# SolderingStation_Processor.net
KiCad netlist of a schematic drawn in Altium Designer
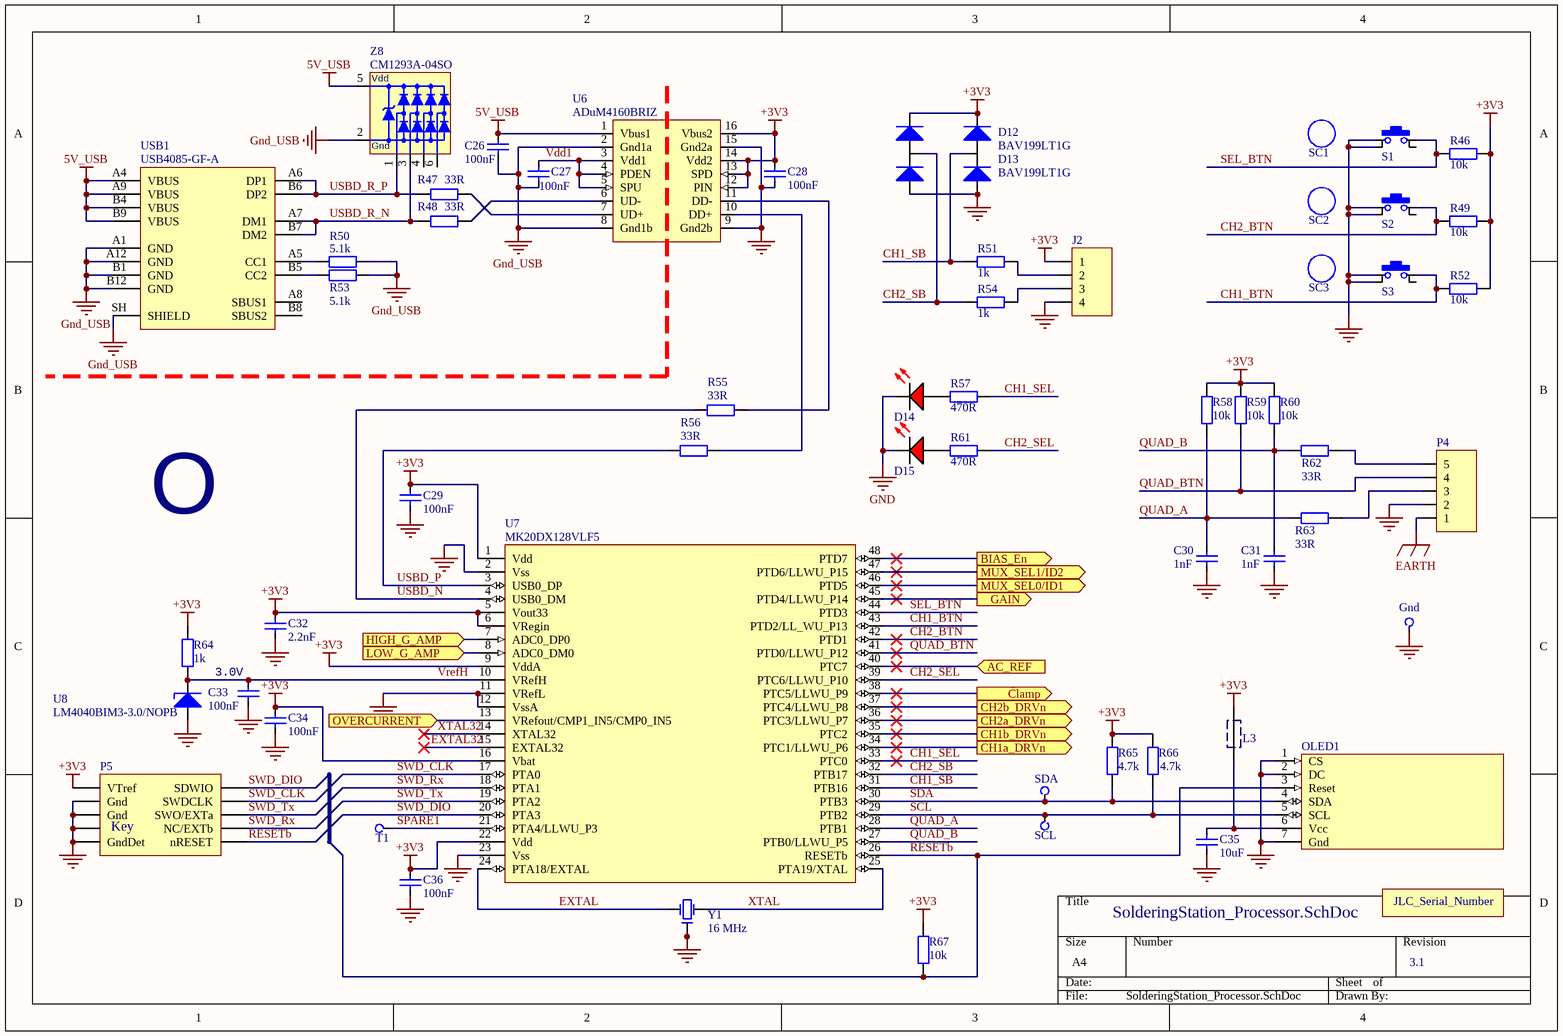
[diagram p0: SolderingStation_Processor.SchDoc]

(export (version "E")
  (design (tool "Eeschema 10.0.6"))
  (components
    (comp (ref "C26")
      (value "100nF")
      (footprint "CCNP1608-0603_N")
      (description "Capacitor non-polar SMT 0603")
      (fields
        (field (name "MANUFACTURER") "Generic Components")
        (field (name "PUBLISHER") "Altium Hobart Technology Centre")
      )
      (libsource (lib "MyLibrary") (part "Cap_CCNP_0603_100nF"))
    )
    (comp (ref "C27")
      (value "100nF")
      (footprint "CCNP1608-0603_N")
      (description "Capacitor non-polar SMT 0603")
      (fields
        (field (name "MANUFACTURER") "Generic Components")
        (field (name "PUBLISHER") "Altium Hobart Technology Centre")
      )
      (libsource (lib "MyLibrary") (part "Cap_CCNP_0603_100nF"))
    )
    (comp (ref "C28")
      (value "100nF")
      (footprint "CCNP1608-0603_N")
      (description "Capacitor non-polar SMT 0603")
      (fields
        (field (name "MANUFACTURER") "Generic Components")
        (field (name "PUBLISHER") "Altium Hobart Technology Centre")
      )
      (libsource (lib "MyLibrary") (part "Cap_CCNP_0603_100nF"))
    )
    (comp (ref "C29")
      (value "100nF")
      (footprint "CCNP1608-0603_N")
      (description "Capacitor non-polar SMT 0603")
      (fields
        (field (name "MANUFACTURER") "Generic Components")
        (field (name "PUBLISHER") "Altium Hobart Technology Centre")
      )
      (libsource (lib "MyLibrary") (part "Cap_CCNP_0603_100nF"))
    )
    (comp (ref "C30")
      (value "1nF")
      (footprint "CCNP1608-0603_N")
      (description "Capacitor non-polar SMT 0603")
      (fields
        (field (name "MANUFACTURER") "Generic Components")
        (field (name "PUBLISHER") "Altium Hobart Technology Centre")
      )
      (libsource (lib "MyLibrary") (part "Cap_CCNP_0603_1nF"))
    )
    (comp (ref "C31")
      (value "1nF")
      (footprint "CCNP1608-0603_N")
      (description "Capacitor non-polar SMT 0603")
      (fields
        (field (name "MANUFACTURER") "Generic Components")
        (field (name "PUBLISHER") "Altium Hobart Technology Centre")
      )
      (libsource (lib "MyLibrary") (part "Cap_CCNP_0603_1nF"))
    )
    (comp (ref "C32")
      (value "2.2nF")
      (footprint "CCNP1608-0603_N")
      (description "Capacitor non-polar SMT 0603")
      (fields
        (field (name "MANUFACTURER") "Generic Components")
        (field (name "PUBLISHER") "Altium Hobart Technology Centre")
      )
      (libsource (lib "MyLibrary") (part "Cap_CCNP_0603_2u2F"))
    )
    (comp (ref "C33")
      (value "100nF")
      (footprint "CCNP1608-0603_N")
      (description "Capacitor non-polar SMT 0603")
      (fields
        (field (name "MANUFACTURER") "Generic Components")
        (field (name "PUBLISHER") "Altium Hobart Technology Centre")
      )
      (libsource (lib "MyLibrary") (part "Cap_CCNP_0603_100nF"))
    )
    (comp (ref "C34")
      (value "100nF")
      (footprint "CCNP1608-0603_N")
      (description "Capacitor non-polar SMT 0603")
      (fields
        (field (name "MANUFACTURER") "Generic Components")
        (field (name "PUBLISHER") "Altium Hobart Technology Centre")
      )
      (libsource (lib "MyLibrary") (part "Cap_CCNP_0603_100nF"))
    )
    (comp (ref "C35")
      (value "10uF")
      (footprint "CCNP2012-0805")
      (description "Capacitor non-polar SMT 0805")
      (fields
        (field (name "MANUFACTURER") "Generic Components")
        (field (name "PUBLISHER") "Altium Hobart Technology Centre")
      )
      (libsource (lib "MyLibrary") (part "Cap_CCNP_0805_10uF"))
    )
    (comp (ref "C36")
      (value "100nF")
      (footprint "CCNP1608-0603_N")
      (description "Capacitor non-polar SMT 0603")
      (fields
        (field (name "MANUFACTURER") "Generic Components")
        (field (name "PUBLISHER") "Altium Hobart Technology Centre")
      )
      (libsource (lib "MyLibrary") (part "Cap_CCNP_0603_100nF"))
    )
    (comp (ref "D12")
      (value "BAV199LT1G")
      (footprint "SOT23_M")
      (description "Dual Series low-leakage switching diodes, 3-Pin SOT-23")
      (libsource (lib "MySchLib") (part "BAV199LT1G"))
    )
    (comp (ref "D13")
      (value "BAV199LT1G")
      (footprint "SOT23_M")
      (description "Dual Series low-leakage switching diodes, 3-Pin SOT-23")
      (libsource (lib "MySchLib") (part "BAV199LT1G"))
    )
    (comp (ref "D14")
      (value "LED")
      (footprint "LED3MM-RED - 10mm Proud")
      (description "3mm Red LED")
      (fields (field (name "MANUFACTURER") "Generic Components") (field (name "PUBLISHER") "Altium Limited"))
      (libsource (lib "MySchLib") (part "LED_3MM_RED"))
    )
    (comp (ref "D15")
      (value "LED")
      (footprint "LED3MM-RED - 10mm Proud")
      (description "3mm Red LED")
      (fields (field (name "MANUFACTURER") "Generic Components") (field (name "PUBLISHER") "Altium Limited"))
      (libsource (lib "MySchLib") (part "LED_3MM_RED"))
    )
    (comp (ref "Gnd")
      (value "Gnd")
      (footprint "PCBPIN - 0.9mm")
      (description "Test Point")
      (libsource (lib "MySchLib") (part "TP"))
    )
    (comp (ref "J2")
      (value "JST XH Connector, 4-Pin")
      (footprint "jst-b4b-xh-ax")
      (fields (field (name "PUBLISHER") "Altium Limited"))
      (libsource (lib "MyLibrary") (part "JST-B4B-XH-A"))
    )
    (comp (ref "JLC_Serial_Number1")
      (value "JLC_Serial_Number")
      (footprint "JLC_Serial_Number")
      (libsource (lib "MyLibrary") (part "JLC_Serial_Number"))
    )
    (comp (ref "L3")
      (value "Ferrite Bead")
      (footprint "FB2012-0805")
      (description "Ferrite Bead SMT 0805, TDK MPZ2012S102AT, 0.15OHM, 1.5A")
      (libsource (lib "MySchLib") (part "Ferrite Bead 0805"))
    )
    (comp (ref "Logo1")
      (value "OSHW Logo")
      (footprint "OSHW")
      (libsource (lib "MyLibrary") (part "OSHW Logo"))
    )
    (comp (ref "OLED1")
      (value "OLED_Display")
      (footprint "OLED_Display_128x64_2.4inch - no mounting holes")
      (description "OLED Display 128x64 pixels, 2.4inch")
      (libsource (lib "MySchLib") (part "OLED_Display_128x64_2.4inch"))
    )
    (comp (ref "P4")
      (value "Header, 5-Pin")
      (footprint "HDR1X5S")
      (fields (field (name "PUBLISHER") "Altium Limited"))
      (libsource (lib "MyLibrary") (part "Header 1x5"))
    )
    (comp (ref "P5")
      (value "SWD Connector 2x5-Pin")
      (footprint "SWD-2x5-Jig-Header")
      (fields (field (name "PUBLISHER") "Altium Limited"))
      (libsource (lib "MySchLib") (part "SWD2X5_JIG"))
    )
    (comp (ref "R46")
      (value "10k")
      (footprint "CR1608-0603_N")
      (description "Resistor SMT 0603")
      (fields
        (field (name "MANUFACTURER") "Generic Components")
        (field (name "PUBLISHER") "Altium Hobart Technology Centre")
      )
      (libsource (lib "") (part "Res_CR0603_10k_1"))
    )
    (comp (ref "R47")
      (value "33R")
      (footprint "CR1608-0603_N")
      (description "Resistor SMT 0603")
      (fields
        (field (name "MANUFACTURER") "Generic Components")
        (field (name "PUBLISHER") "Altium Hobart Technology Centre")
      )
      (libsource (lib "MyLibrary") (part "Res_CR0603_33R"))
    )
    (comp (ref "R48")
      (value "33R")
      (footprint "CR1608-0603_N")
      (description "Resistor SMT 0603")
      (fields
        (field (name "MANUFACTURER") "Generic Components")
        (field (name "PUBLISHER") "Altium Hobart Technology Centre")
      )
      (libsource (lib "MyLibrary") (part "Res_CR0603_33R"))
    )
    (comp (ref "R49")
      (value "10k")
      (footprint "CR1608-0603_N")
      (description "Resistor SMT 0603")
      (fields
        (field (name "MANUFACTURER") "Generic Components")
        (field (name "PUBLISHER") "Altium Hobart Technology Centre")
      )
      (libsource (lib "") (part "Res_CR0603_10k_1"))
    )
    (comp (ref "R50")
      (value "5.1k")
      (footprint "CR1608-0603_N")
      (description "Resistor SMT 0603")
      (fields
        (field (name "MANUFACTURER") "Generic Components")
        (field (name "PUBLISHER") "Altium Hobart Technology Centre")
      )
      (libsource (lib "MyLibrary") (part "Res_CR0603_5k1"))
    )
    (comp (ref "R51")
      (value "1k")
      (footprint "CR1608-0603_N")
      (description "Resistor SMT 0603")
      (fields
        (field (name "MANUFACTURER") "Generic Components")
        (field (name "PUBLISHER") "Altium Hobart Technology Centre")
      )
      (libsource (lib "") (part "Res_CR0603_1k_1"))
    )
    (comp (ref "R52")
      (value "10k")
      (footprint "CR1608-0603_N")
      (description "Resistor SMT 0603")
      (fields
        (field (name "MANUFACTURER") "Generic Components")
        (field (name "PUBLISHER") "Altium Hobart Technology Centre")
      )
      (libsource (lib "") (part "Res_CR0603_10k_1"))
    )
    (comp (ref "R53")
      (value "5.1k")
      (footprint "CR1608-0603_N")
      (description "Resistor SMT 0603")
      (fields
        (field (name "MANUFACTURER") "Generic Components")
        (field (name "PUBLISHER") "Altium Hobart Technology Centre")
      )
      (libsource (lib "MyLibrary") (part "Res_CR0603_5k1"))
    )
    (comp (ref "R54")
      (value "1k")
      (footprint "CR1608-0603_N")
      (description "Resistor SMT 0603")
      (fields
        (field (name "MANUFACTURER") "Generic Components")
        (field (name "PUBLISHER") "Altium Hobart Technology Centre")
      )
      (libsource (lib "") (part "Res_CR0603_1k_1"))
    )
    (comp (ref "R55")
      (value "33R")
      (footprint "CR1608-0603_N")
      (description "Resistor SMT 0603")
      (fields
        (field (name "MANUFACTURER") "Generic Components")
        (field (name "PUBLISHER") "Altium Hobart Technology Centre")
      )
      (libsource (lib "MyLibrary") (part "Res_CR0603_33R"))
    )
    (comp (ref "R56")
      (value "33R")
      (footprint "CR1608-0603_N")
      (description "Resistor SMT 0603")
      (fields
        (field (name "MANUFACTURER") "Generic Components")
        (field (name "PUBLISHER") "Altium Hobart Technology Centre")
      )
      (libsource (lib "MyLibrary") (part "Res_CR0603_33R"))
    )
    (comp (ref "R57")
      (value "470R")
      (footprint "CR1608-0603_N")
      (description "Resistor SMT 0603")
      (fields
        (field (name "MANUFACTURER") "Generic Components")
        (field (name "PUBLISHER") "Altium Hobart Technology Centre")
      )
      (libsource (lib "MyLibrary") (part "Res_CR0603_470R"))
    )
    (comp (ref "R58")
      (value "10k")
      (footprint "CR1608-0603_N")
      (description "Resistor SMT 0603")
      (fields
        (field (name "MANUFACTURER") "Generic Components")
        (field (name "PUBLISHER") "Altium Hobart Technology Centre")
      )
      (libsource (lib "MyLibrary") (part "Res_CR0603_10k"))
    )
    (comp (ref "R59")
      (value "10k")
      (footprint "CR1608-0603_N")
      (description "Resistor SMT 0603")
      (fields
        (field (name "MANUFACTURER") "Generic Components")
        (field (name "PUBLISHER") "Altium Hobart Technology Centre")
      )
      (libsource (lib "MyLibrary") (part "Res_CR0603_10k"))
    )
    (comp (ref "R60")
      (value "10k")
      (footprint "CR1608-0603_N")
      (description "Resistor SMT 0603")
      (fields
        (field (name "MANUFACTURER") "Generic Components")
        (field (name "PUBLISHER") "Altium Hobart Technology Centre")
      )
      (libsource (lib "MyLibrary") (part "Res_CR0603_10k"))
    )
    (comp (ref "R61")
      (value "470R")
      (footprint "CR1608-0603_N")
      (description "Resistor SMT 0603")
      (fields
        (field (name "MANUFACTURER") "Generic Components")
        (field (name "PUBLISHER") "Altium Hobart Technology Centre")
      )
      (libsource (lib "") (part "Res_CR0603_470R_1"))
    )
    (comp (ref "R62")
      (value "33R")
      (footprint "CR1608-0603_N")
      (description "Resistor SMT 0603")
      (fields
        (field (name "MANUFACTURER") "Generic Components")
        (field (name "PUBLISHER") "Altium Hobart Technology Centre")
      )
      (libsource (lib "MyLibrary") (part "Res_CR0603_33R"))
    )
    (comp (ref "R63")
      (value "33R")
      (footprint "CR1608-0603_N")
      (description "Resistor SMT 0603")
      (fields
        (field (name "MANUFACTURER") "Generic Components")
        (field (name "PUBLISHER") "Altium Hobart Technology Centre")
      )
      (libsource (lib "MyLibrary") (part "Res_CR0603_33R"))
    )
    (comp (ref "R64")
      (value "1k")
      (footprint "CR1608-0603_N")
      (description "Resistor SMT 0603")
      (fields
        (field (name "MANUFACTURER") "Generic Components")
        (field (name "PUBLISHER") "Altium Hobart Technology Centre")
      )
      (libsource (lib "MyLibrary") (part "Res_CR0603_1k"))
    )
    (comp (ref "R65")
      (value "4.7k")
      (footprint "CR1608-0603_N")
      (description "Resistor SMT 0603")
      (fields
        (field (name "MANUFACTURER") "Generic Components")
        (field (name "PUBLISHER") "Altium Hobart Technology Centre")
      )
      (libsource (lib "MyLibrary") (part "Res_CR0603_4k7"))
    )
    (comp (ref "R66")
      (value "4.7k")
      (footprint "CR1608-0603_N")
      (description "Resistor SMT 0603")
      (fields
        (field (name "MANUFACTURER") "Generic Components")
        (field (name "PUBLISHER") "Altium Hobart Technology Centre")
      )
      (libsource (lib "MyLibrary") (part "Res_CR0603_4k7"))
    )
    (comp (ref "R67")
      (value "10k")
      (footprint "CR1608-0603_N")
      (description "Resistor SMT 0603")
      (fields
        (field (name "MANUFACTURER") "Generic Components")
        (field (name "PUBLISHER") "Altium Hobart Technology Centre")
      )
      (libsource (lib "MyLibrary") (part "Res_CR0603_10k"))
    )
    (comp (ref "S1")
      (value "SW_PB-B3F1052")
      (footprint "SW_MIN_PB-B3F1052")
      (description "Switch miniature push-button")
      (fields (field (name "MANUFACTURER") "Generic Components") (field (name "PUBLISHER") "Altium Limited"))
      (libsource (lib "MySchLib") (part "SW_PB-B3F1052"))
    )
    (comp (ref "S2")
      (value "SW_PB-B3F1052")
      (footprint "SW_MIN_PB-B3F1052")
      (description "Switch miniature push-button")
      (fields (field (name "MANUFACTURER") "Generic Components") (field (name "PUBLISHER") "Altium Limited"))
      (libsource (lib "MySchLib") (part "SW_PB-B3F1052"))
    )
    (comp (ref "S3")
      (value "SW_PB-B3F1052")
      (footprint "SW_MIN_PB-B3F1052")
      (description "Switch miniature push-button")
      (fields (field (name "MANUFACTURER") "Generic Components") (field (name "PUBLISHER") "Altium Limited"))
      (libsource (lib "MySchLib") (part "SW_PB-B3F1052"))
    )
    (comp (ref "SC1")
      (value "B32-2010")
      (footprint "SW-CAP-B32-2010")
      (description "Switch Cap")
      (libsource (lib "MySchLib") (part "Switch-Cap - B32-2010"))
    )
    (comp (ref "SC2")
      (value "B32-2010")
      (footprint "SW-CAP-B32-2010")
      (description "Switch Cap")
      (libsource (lib "MySchLib") (part "Switch-Cap - B32-2010"))
    )
    (comp (ref "SC3")
      (value "B32-2010")
      (footprint "SW-CAP-B32-2010")
      (description "Switch Cap")
      (libsource (lib "MySchLib") (part "Switch-Cap - B32-2010"))
    )
    (comp (ref "SCL")
      (value "SCL")
      (footprint "PCBPIN - 0.9mm")
      (description "Test Point")
      (libsource (lib "MySchLib") (part "TP"))
    )
    (comp (ref "SDA")
      (value "SDA")
      (footprint "PCBPIN - 0.9mm")
      (description "Test Point")
      (libsource (lib "MySchLib") (part "TP"))
    )
    (comp (ref "T1")
      (value "PTA4")
      (footprint "PCBPIN - 0.9mm")
      (description "Test Point")
      (libsource (lib "MySchLib") (part "TP"))
    )
    (comp (ref "U6")
      (value "ADuM4160BRIZ")
      (footprint "SOIC127P1030-16M")
      (description "Full/Low Speed 5 kV USB Digital Isolator")
      (libsource (lib "MySchLib") (part "ADuM4160BRIZ"))
    )
    (comp (ref "U7")
      (value "MK20DX128VLF5")
      (footprint "TSQFP50P900X900-48M")
      (description "Kinetis K20: 50MHz Cortex-M4 Performance MCU, 160KB Flash, 16KB SRAM, Full-Speed USB, 48-LQFP")
      (libsource (lib "MySchLib") (part "MK20DX128VLF5"))
    )
    (comp (ref "U8")
      (value "LM4040BIM3-3.0/NOPB")
      (footprint "SOT23_M")
      (description "IC 2.5V VREF SHUNT 0.2% SOT23-3")
      (libsource (lib "MySchLib") (part "LM4040BIM3-2.5/NOPB"))
    )
    (comp (ref "USB1")
      (value "USB4085-GF-A")
      (footprint "USB4085-GF-A")
      (description "USB-C, USB 2.0 Receptacle Connector 16 Position Through Hole, Right Angle")
      (fields (field (name "DIGIKEY PART NUMBER") "2073-USB4085-GF-ACT-ND"))
      (libsource (lib "MyLibrary") (part "USB4085-GF-A"))
    )
    (comp (ref "Y1")
      (value "16 MHz")
      (footprint "Crystal_SMD_3.2x2.5")
      (description "Crystal SMD 3.2 x 2.5 x 0.7 mm")
      (fields
        (field (name "MANUFACTURER") "Generic Components")
        (field (name "PUBLISHER") "Altium Hobart Technology Centre")
      )
      (libsource (lib "MyLibrary") (part "Crystal 16MHz"))
    )
    (comp (ref "Z8")
      (value "CM1293A-04SO")
      (footprint "SOT457_M - 180")
      (description "Ultra low capacitance quadruple rail-to-rail ESD protection")
      (libsource (lib "MySchLib") (part "CM1293A-04SO"))
    )
  )
  (nets
    (net (code "1") (name "+3V3") (class "Default")
      (node (ref "C28") (pin "2") (pinfunction "2_2") (pintype "passive"))
      (node (ref "C29") (pin "2") (pinfunction "2_2") (pintype "passive"))
      (node (ref "C32") (pin "2") (pinfunction "2_2") (pintype "passive"))
      (node (ref "C34") (pin "2") (pinfunction "2_2") (pintype "passive"))
      (node (ref "C36") (pin "2") (pinfunction "2_2") (pintype "passive"))
      (node (ref "D12") (pin "2") (pinfunction "A2_2") (pintype "passive"))
      (node (ref "D13") (pin "2") (pinfunction "A2_2") (pintype "passive"))
      (node (ref "J2") (pin "1") (pinfunction "1_1") (pintype "passive"))
      (node (ref "L3") (pin "1") (pinfunction "1_1") (pintype "passive"))
      (node (ref "P5") (pin "1") (pinfunction "VTref_1") (pintype "passive"))
      (node (ref "R46") (pin "2") (pinfunction "2_2") (pintype "passive"))
      (node (ref "R49") (pin "2") (pinfunction "2_2") (pintype "passive"))
      (node (ref "R52") (pin "2") (pinfunction "2_2") (pintype "passive"))
      (node (ref "R58") (pin "2") (pinfunction "2_2") (pintype "passive"))
      (node (ref "R59") (pin "2") (pinfunction "2_2") (pintype "passive"))
      (node (ref "R60") (pin "2") (pinfunction "2_2") (pintype "passive"))
      (node (ref "R64") (pin "1") (pinfunction "1_1") (pintype "passive"))
      (node (ref "R65") (pin "2") (pinfunction "2_2") (pintype "passive"))
      (node (ref "R66") (pin "2") (pinfunction "2_2") (pintype "passive"))
      (node (ref "R67") (pin "2") (pinfunction "2_2") (pintype "passive"))
      (node (ref "U6") (pin "12") (pinfunction "PIN_12") (pintype "input"))
      (node (ref "U6") (pin "13") (pinfunction "SPD_13") (pintype "input"))
      (node (ref "U6") (pin "14") (pinfunction "Vdd2_14") (pintype "power_in"))
      (node (ref "U6") (pin "16") (pinfunction "Vbus2_16") (pintype "power_in"))
      (node (ref "U7") (pin "1") (pinfunction "Vdd_1") (pintype "power_in"))
      (node (ref "U7") (pin "16") (pinfunction "Vbat_16") (pintype "passive"))
      (node (ref "U7") (pin "22") (pinfunction "Vdd_22") (pintype "power_in"))
      (node (ref "U7") (pin "5") (pinfunction "Vout33_5") (pintype "power_in"))
      (node (ref "U7") (pin "6") (pinfunction "VRegin_6") (pintype "passive"))
      (node (ref "U7") (pin "9") (pinfunction "VddA_9") (pintype "power_in"))
    )
    (net (code "2") (name "/AC_REF") (class "Default")
      (node (ref "U7") (pin "40") (pinfunction "PTC7_40") (pintype "bidirectional"))
    )
    (net (code "3") (name "/BIAS_En") (class "Default")
      (node (ref "U7") (pin "48") (pinfunction "PTD7_48") (pintype "bidirectional"))
    )
    (net (code "4") (name "/CH1_BTN") (class "Default")
      (node (ref "R52") (pin "1") (pinfunction "1_1") (pintype "passive"))
      (node (ref "S3") (pin "2") (pinfunction "2_2") (pintype "passive"))
      (node (ref "U7") (pin "43") (pinfunction "PTD2/LL_WU_P13_43") (pintype "bidirectional"))
    )
    (net (code "5") (name "/CH1_SB") (class "Default")
      (node (ref "D13") (pin "3") (pinfunction "K_3") (pintype "passive"))
      (node (ref "R51") (pin "1") (pinfunction "1_1") (pintype "passive"))
      (node (ref "U7") (pin "31") (pinfunction "PTB16_31") (pintype "bidirectional"))
    )
    (net (code "6") (name "/CH1_SEL") (class "Default")
      (node (ref "R57") (pin "1") (pinfunction "1_1") (pintype "passive"))
      (node (ref "U7") (pin "33") (pinfunction "PTC0_33") (pintype "bidirectional"))
    )
    (net (code "7") (name "/CH1a_DRVn") (class "Default")
      (node (ref "U7") (pin "34") (pinfunction "PTC1/LLWU_P6_34") (pintype "bidirectional"))
    )
    (net (code "8") (name "/CH1b_DRVn") (class "Default")
      (node (ref "U7") (pin "35") (pinfunction "PTC2_35") (pintype "bidirectional"))
    )
    (net (code "9") (name "/CH2_BTN") (class "Default")
      (node (ref "R49") (pin "1") (pinfunction "1_1") (pintype "passive"))
      (node (ref "S2") (pin "2") (pinfunction "2_2") (pintype "passive"))
      (node (ref "U7") (pin "42") (pinfunction "PTD1_42") (pintype "bidirectional"))
    )
    (net (code "10") (name "/CH2_SB") (class "Default")
      (node (ref "D12") (pin "3") (pinfunction "K_3") (pintype "passive"))
      (node (ref "R54") (pin "1") (pinfunction "1_1") (pintype "passive"))
      (node (ref "U7") (pin "32") (pinfunction "PTB17_32") (pintype "bidirectional"))
    )
    (net (code "11") (name "/CH2_SEL") (class "Default")
      (node (ref "R61") (pin "2") (pinfunction "2_2") (pintype "passive"))
      (node (ref "U7") (pin "39") (pinfunction "PTC6/LLWU_P10_39") (pintype "bidirectional"))
    )
    (net (code "12") (name "/CH2a_DRVn") (class "Default")
      (node (ref "U7") (pin "36") (pinfunction "PTC3/LLWU_P7_36") (pintype "bidirectional"))
    )
    (net (code "13") (name "/CH2b_DRVn") (class "Default")
      (node (ref "U7") (pin "37") (pinfunction "PTC4/LLWU_P8_37") (pintype "bidirectional"))
    )
    (net (code "14") (name "/Clamp") (class "Default")
      (node (ref "U7") (pin "38") (pinfunction "PTC5/LLWU_P9_38") (pintype "bidirectional"))
    )
    (net (code "15") (name "/EXTAL") (class "Default")
      (node (ref "U7") (pin "24") (pinfunction "PTA18/EXTAL_24") (pintype "bidirectional"))
      (node (ref "Y1") (pin "3") (pinfunction "OSC2_3") (pintype "passive"))
    )
    (net (code "16") (name "/EXTAL32") (class "Default")
      (node (ref "U7") (pin "15") (pinfunction "EXTAL32_15") (pintype "passive+no_connect"))
    )
    (net (code "17") (name "/GAIN") (class "Default")
      (node (ref "U7") (pin "45") (pinfunction "PTD4/LLWU_P14_45") (pintype "bidirectional"))
    )
    (net (code "18") (name "/HIGH_G_AMP") (class "Default")
      (node (ref "U7") (pin "7") (pinfunction "ADC0_DP0_7") (pintype "input"))
    )
    (net (code "19") (name "/LOW_G_AMP") (class "Default")
      (node (ref "U7") (pin "8") (pinfunction "ADC0_DM0_8") (pintype "input"))
    )
    (net (code "20") (name "/MUX_SEL0{slash}ID1") (class "Default")
      (node (ref "U7") (pin "46") (pinfunction "PTD5_46") (pintype "bidirectional"))
    )
    (net (code "21") (name "/MUX_SEL1{slash}ID2") (class "Default")
      (node (ref "U7") (pin "47") (pinfunction "PTD6/LLWU_P15_47") (pintype "bidirectional"))
    )
    (net (code "22") (name "/OVERCURRENT") (class "Default")
      (node (ref "U7") (pin "13") (pinfunction "VRefout/CMP1_IN5/CMP0_IN5_13") (pintype "passive"))
    )
    (net (code "23") (name "/QUAD_A") (class "Default")
      (node (ref "C30") (pin "2") (pinfunction "2_2") (pintype "passive"))
      (node (ref "R58") (pin "1") (pinfunction "1_1") (pintype "passive"))
      (node (ref "R63") (pin "2") (pinfunction "2_2") (pintype "passive"))
      (node (ref "U7") (pin "28") (pinfunction "PTB1_28") (pintype "bidirectional"))
    )
    (net (code "24") (name "/QUAD_B") (class "Default")
      (node (ref "C31") (pin "2") (pinfunction "2_2") (pintype "passive"))
      (node (ref "R60") (pin "1") (pinfunction "1_1") (pintype "passive"))
      (node (ref "R62") (pin "2") (pinfunction "2_2") (pintype "passive"))
      (node (ref "U7") (pin "27") (pinfunction "PTB0/LLWU_P5_27") (pintype "bidirectional"))
    )
    (net (code "25") (name "/QUAD_BTN") (class "Default")
      (node (ref "P4") (pin "4") (pinfunction "4_4") (pintype "passive"))
      (node (ref "R59") (pin "1") (pinfunction "1_1") (pintype "passive"))
      (node (ref "U7") (pin "41") (pinfunction "PTD0/LLWU_P12_41") (pintype "bidirectional"))
    )
    (net (code "26") (name "/RESETb") (class "Default")
      (node (ref "OLED1") (pin "3") (pinfunction "Reset_3") (pintype "input"))
      (node (ref "P5") (pin "10") (pinfunction "nRESET_10") (pintype "passive"))
      (node (ref "R67") (pin "1") (pinfunction "1_1") (pintype "passive"))
      (node (ref "U7") (pin "26") (pinfunction "RESETb_26") (pintype "bidirectional"))
    )
    (net (code "27") (name "/SCL") (class "Default")
      (node (ref "OLED1") (pin "5") (pinfunction "SCL_5") (pintype "bidirectional"))
      (node (ref "R66") (pin "1") (pinfunction "1_1") (pintype "passive"))
      (node (ref "SCL") (pin "1") (pinfunction "TP_1") (pintype "passive"))
      (node (ref "U7") (pin "29") (pinfunction "PTB2_29") (pintype "bidirectional"))
    )
    (net (code "28") (name "/SDA") (class "Default")
      (node (ref "OLED1") (pin "4") (pinfunction "SDA_4") (pintype "bidirectional"))
      (node (ref "R65") (pin "1") (pinfunction "1_1") (pintype "passive"))
      (node (ref "SDA") (pin "1") (pinfunction "TP_1") (pintype "passive"))
      (node (ref "U7") (pin "30") (pinfunction "PTB3_30") (pintype "bidirectional"))
    )
    (net (code "29") (name "/SEL_BTN") (class "Default")
      (node (ref "R46") (pin "1") (pinfunction "1_1") (pintype "passive"))
      (node (ref "S1") (pin "2") (pinfunction "2_2") (pintype "passive"))
      (node (ref "U7") (pin "44") (pinfunction "PTD3_44") (pintype "bidirectional"))
    )
    (net (code "30") (name "/SPARE1") (class "Default")
      (node (ref "T1") (pin "1") (pinfunction "TP_1") (pintype "passive"))
      (node (ref "U7") (pin "21") (pinfunction "PTA4/LLWU_P3_21") (pintype "bidirectional"))
    )
    (net (code "31") (name "/SWD_CLK") (class "Default")
      (node (ref "P5") (pin "4") (pinfunction "SWDCLK_4") (pintype "passive"))
      (node (ref "U7") (pin "17") (pinfunction "PTA0_17") (pintype "bidirectional"))
    )
    (net (code "32") (name "/SWD_DIO") (class "Default")
      (node (ref "P5") (pin "2") (pinfunction "SDWIO_2") (pintype "passive"))
      (node (ref "U7") (pin "20") (pinfunction "PTA3_20") (pintype "bidirectional"))
    )
    (net (code "33") (name "/SWD_Rx") (class "Default")
      (node (ref "P5") (pin "8") (pinfunction "NC/EXTb_8") (pintype "passive"))
      (node (ref "U7") (pin "18") (pinfunction "PTA1_18") (pintype "bidirectional"))
    )
    (net (code "34") (name "/SWD_Tx") (class "Default")
      (node (ref "P5") (pin "6") (pinfunction "SWO/EXTa_6") (pintype "passive"))
      (node (ref "U7") (pin "19") (pinfunction "PTA2_19") (pintype "bidirectional"))
    )
    (net (code "35") (name "/USBD_N") (class "Default")
      (node (ref "R55") (pin "2") (pinfunction "2_2") (pintype "passive"))
      (node (ref "U7") (pin "4") (pinfunction "USB0_DM_4") (pintype "bidirectional"))
    )
    (net (code "36") (name "/USBD_P") (class "Default")
      (node (ref "R56") (pin "2") (pinfunction "2_2") (pintype "passive"))
      (node (ref "U7") (pin "3") (pinfunction "USB0_DP_3") (pintype "bidirectional"))
    )
    (net (code "37") (name "/USBD_R_N") (class "Default")
      (node (ref "R48") (pin "2") (pinfunction "2_2") (pintype "passive"))
      (node (ref "USB1") (pin "A7") (pinfunction "DM1_A7") (pintype "passive"))
      (node (ref "USB1") (pin "B7") (pinfunction "DM2_B7") (pintype "passive"))
      (node (ref "Z8") (pin "3") (pintype "passive"))
    )
    (net (code "38") (name "/USBD_R_P") (class "Default")
      (node (ref "R47") (pin "2") (pinfunction "2_2") (pintype "passive"))
      (node (ref "USB1") (pin "A6") (pinfunction "DP1_A6") (pintype "passive"))
      (node (ref "USB1") (pin "B6") (pinfunction "DP2_B6") (pintype "passive"))
      (node (ref "Z8") (pin "1") (pintype "passive"))
    )
    (net (code "39") (name "/Vdd1") (class "Default")
      (node (ref "C27") (pin "2") (pinfunction "2_2") (pintype "passive"))
      (node (ref "U6") (pin "3") (pinfunction "Vdd1_3") (pintype "power_in"))
      (node (ref "U6") (pin "4") (pinfunction "PDEN_4") (pintype "input"))
      (node (ref "U6") (pin "5") (pinfunction "SPU_5") (pintype "input"))
    )
    (net (code "40") (name "/VrefH") (class "Default")
      (node (ref "C33") (pin "2") (pinfunction "2_2") (pintype "passive"))
      (node (ref "R64") (pin "2") (pinfunction "2_2") (pintype "passive"))
      (node (ref "U7") (pin "10") (pinfunction "VRefH_10") (pintype "passive"))
      (node (ref "U8") (pin "1") (pinfunction "K_1") (pintype "passive"))
    )
    (net (code "41") (name "/XTAL") (class "Default")
      (node (ref "U7") (pin "25") (pinfunction "PTA19/XTAL_25") (pintype "bidirectional"))
      (node (ref "Y1") (pin "1") (pinfunction "OSC1_1") (pintype "passive"))
    )
    (net (code "42") (name "/XTAL32") (class "Default")
      (node (ref "U7") (pin "14") (pinfunction "XTAL32_14") (pintype "passive+no_connect"))
    )
    (net (code "43") (name "5V_USB") (class "Default")
      (node (ref "C26") (pin "2") (pinfunction "2_2") (pintype "passive"))
      (node (ref "U6") (pin "1") (pinfunction "Vbus1_1") (pintype "power_in"))
      (node (ref "USB1") (pin "A4") (pinfunction "VBUS_A4") (pintype "passive"))
      (node (ref "USB1") (pin "A9") (pinfunction "VBUS_A9") (pintype "passive"))
      (node (ref "USB1") (pin "B4") (pinfunction "VBUS_B4") (pintype "passive"))
      (node (ref "USB1") (pin "B9") (pinfunction "VBUS_B9") (pintype "passive"))
      (node (ref "Z8") (pin "5") (pinfunction "Vp_5") (pintype "passive"))
    )
    (net (code "44") (name "EARTH") (class "Default")
      (node (ref "P4") (pin "1") (pinfunction "1_1") (pintype "passive"))
    )
    (net (code "45") (name "GND") (class "Default")
      (node (ref "C28") (pin "1") (pinfunction "1_1") (pintype "passive"))
      (node (ref "C29") (pin "1") (pinfunction "1_1") (pintype "passive"))
      (node (ref "C30") (pin "1") (pinfunction "1_1") (pintype "passive"))
      (node (ref "C31") (pin "1") (pinfunction "1_1") (pintype "passive"))
      (node (ref "C32") (pin "1") (pinfunction "1_1") (pintype "passive"))
      (node (ref "C33") (pin "1") (pinfunction "1_1") (pintype "passive"))
      (node (ref "C34") (pin "1") (pinfunction "1_1") (pintype "passive"))
      (node (ref "C35") (pin "1") (pinfunction "1_1") (pintype "passive"))
      (node (ref "C36") (pin "1") (pinfunction "1_1") (pintype "passive"))
      (node (ref "D12") (pin "1") (pinfunction "A1_1") (pintype "passive"))
      (node (ref "D13") (pin "1") (pinfunction "A1_1") (pintype "passive"))
      (node (ref "D14") (pin "K") (pinfunction "K_K") (pintype "passive"))
      (node (ref "D15") (pin "K") (pinfunction "K_K") (pintype "passive"))
      (node (ref "Gnd") (pin "1") (pinfunction "TP_1") (pintype "passive"))
      (node (ref "J2") (pin "4") (pinfunction "4_4") (pintype "passive"))
      (node (ref "OLED1") (pin "1") (pinfunction "CS_1") (pintype "input"))
      (node (ref "OLED1") (pin "2") (pinfunction "DC_2") (pintype "input"))
      (node (ref "OLED1") (pin "7") (pinfunction "Gnd_7") (pintype "power_in"))
      (node (ref "P4") (pin "2") (pinfunction "2_2") (pintype "passive"))
      (node (ref "P5") (pin "0") (pinfunction "Pins_0") (pintype "power_in"))
      (node (ref "P5") (pin "3") (pinfunction "Gnd_3") (pintype "passive"))
      (node (ref "P5") (pin "5") (pinfunction "Gnd_5") (pintype "passive"))
      (node (ref "P5") (pin "9") (pinfunction "GndDet_9") (pintype "passive"))
      (node (ref "S1") (pin "1") (pinfunction "1_1") (pintype "passive"))
      (node (ref "S1") (pin "1b") (pinfunction "1b_1b") (pintype "passive"))
      (node (ref "S2") (pin "1") (pinfunction "1_1") (pintype "passive"))
      (node (ref "S2") (pin "1b") (pinfunction "1b_1b") (pintype "passive"))
      (node (ref "S3") (pin "1") (pinfunction "1_1") (pintype "passive"))
      (node (ref "S3") (pin "1b") (pinfunction "1b_1b") (pintype "passive"))
      (node (ref "U6") (pin "15") (pinfunction "Gnd2a_15") (pintype "power_in"))
      (node (ref "U6") (pin "9") (pinfunction "Gnd2b_9") (pintype "power_in"))
      (node (ref "U7") (pin "11") (pinfunction "VRefL_11") (pintype "passive"))
      (node (ref "U7") (pin "12") (pinfunction "VssA_12") (pintype "power_in"))
      (node (ref "U7") (pin "2") (pinfunction "Vss_2") (pintype "power_in"))
      (node (ref "U7") (pin "23") (pinfunction "Vss_23") (pintype "power_in"))
      (node (ref "U8") (pin "2") (pinfunction "A_2") (pintype "passive"))
      (node (ref "Y1") (pin "2") (pinfunction "Gnd_2") (pintype "passive"))
      (node (ref "Y1") (pin "4") (pinfunction "Gnd_4") (pintype "passive"))
    )
    (net (code "46") (name "Gnd_USB") (class "Default")
      (node (ref "C26") (pin "1") (pinfunction "1_1") (pintype "passive"))
      (node (ref "C27") (pin "1") (pinfunction "1_1") (pintype "passive"))
      (node (ref "R50") (pin "2") (pinfunction "2_2") (pintype "passive"))
      (node (ref "R53") (pin "2") (pinfunction "2_2") (pintype "passive"))
      (node (ref "U6") (pin "2") (pinfunction "Gnd1a_2") (pintype "power_in"))
      (node (ref "U6") (pin "8") (pinfunction "Gnd1b_8") (pintype "power_in"))
      (node (ref "USB1") (pin "A1") (pinfunction "GND_A1") (pintype "passive"))
      (node (ref "USB1") (pin "A12") (pinfunction "GND_A12") (pintype "passive"))
      (node (ref "USB1") (pin "B1") (pinfunction "GND_B1") (pintype "passive"))
      (node (ref "USB1") (pin "B12") (pinfunction "GND_B12") (pintype "passive"))
      (node (ref "USB1") (pin "SH") (pinfunction "SHIELD_SH") (pintype "passive"))
      (node (ref "Z8") (pin "2") (pinfunction "Vn_2") (pintype "passive"))
    )
    (net (code "47") (name "Net-(D14-PadA)") (class "Default")
      (node (ref "D14") (pin "A") (pinfunction "A_A") (pintype "passive"))
      (node (ref "R57") (pin "2") (pinfunction "2_2") (pintype "passive"))
    )
    (net (code "48") (name "Net-(D15-PadA)") (class "Default")
      (node (ref "D15") (pin "A") (pinfunction "A_A") (pintype "passive"))
      (node (ref "R61") (pin "1") (pinfunction "1_1") (pintype "passive"))
    )
    (net (code "49") (name "Net-(J2-Pad2)") (class "Default")
      (node (ref "J2") (pin "2") (pinfunction "2_2") (pintype "passive"))
      (node (ref "R51") (pin "2") (pinfunction "2_2") (pintype "passive"))
    )
    (net (code "50") (name "Net-(J2-Pad3)") (class "Default")
      (node (ref "J2") (pin "3") (pinfunction "3_3") (pintype "passive"))
      (node (ref "R54") (pin "2") (pinfunction "2_2") (pintype "passive"))
    )
    (net (code "51") (name "Net-(OLED1-Vcc)") (class "Default")
      (node (ref "C35") (pin "2") (pinfunction "2_2") (pintype "passive"))
      (node (ref "L3") (pin "2") (pinfunction "2_2") (pintype "passive"))
      (node (ref "OLED1") (pin "6") (pinfunction "Vcc_6") (pintype "power_in"))
    )
    (net (code "52") (name "Net-(P4-Pad3)") (class "Default")
      (node (ref "P4") (pin "3") (pinfunction "3_3") (pintype "passive"))
      (node (ref "R63") (pin "1") (pinfunction "1_1") (pintype "passive"))
    )
    (net (code "53") (name "Net-(P4-Pad5)") (class "Default")
      (node (ref "P4") (pin "5") (pinfunction "5_5") (pintype "passive"))
      (node (ref "R62") (pin "1") (pinfunction "1_1") (pintype "passive"))
    )
    (net (code "54") (name "Net-(U6-DD+)") (class "Default")
      (node (ref "R56") (pin "1") (pinfunction "1_1") (pintype "passive"))
      (node (ref "U6") (pin "10") (pinfunction "DD+_10") (pintype "bidirectional"))
    )
    (net (code "55") (name "Net-(U6-DD-)") (class "Default")
      (node (ref "R55") (pin "1") (pinfunction "1_1") (pintype "passive"))
      (node (ref "U6") (pin "11") (pinfunction "DD-_11") (pintype "bidirectional"))
    )
    (net (code "56") (name "Net-(U6-UD+)") (class "Default")
      (node (ref "R47") (pin "1") (pinfunction "1_1") (pintype "passive"))
      (node (ref "U6") (pin "7") (pinfunction "UD+_7") (pintype "bidirectional"))
    )
    (net (code "57") (name "Net-(U6-UD-)") (class "Default")
      (node (ref "R48") (pin "1") (pinfunction "1_1") (pintype "passive"))
      (node (ref "U6") (pin "6") (pinfunction "UD-_6") (pintype "bidirectional"))
    )
    (net (code "58") (name "Net-(USB1-CC1)") (class "Default")
      (node (ref "R50") (pin "1") (pinfunction "1_1") (pintype "passive"))
      (node (ref "USB1") (pin "A5") (pinfunction "CC1_A5") (pintype "passive"))
    )
    (net (code "59") (name "Net-(USB1-CC2)") (class "Default")
      (node (ref "R53") (pin "1") (pinfunction "1_1") (pintype "passive"))
      (node (ref "USB1") (pin "B5") (pinfunction "CC2_B5") (pintype "passive"))
    )
    (net (code "60") (name "unconnected-(S1-Pad2b)") (class "Default")
      (node (ref "S1") (pin "2b") (pinfunction "2b_2b") (pintype "passive"))
    )
    (net (code "61") (name "unconnected-(S2-Pad2b)") (class "Default")
      (node (ref "S2") (pin "2b") (pinfunction "2b_2b") (pintype "passive"))
    )
    (net (code "62") (name "unconnected-(S3-Pad2b)") (class "Default")
      (node (ref "S3") (pin "2b") (pinfunction "2b_2b") (pintype "passive"))
    )
    (net (code "63") (name "unconnected-(U8-NC-Pad3)") (class "Default")
      (node (ref "U8") (pin "3") (pinfunction "NC_3") (pintype "passive"))
    )
    (net (code "64") (name "unconnected-(USB1-SBUS1-PadA8)") (class "Default")
      (node (ref "USB1") (pin "A8") (pinfunction "SBUS1_A8") (pintype "passive"))
    )
    (net (code "65") (name "unconnected-(USB1-SBUS2-PadB8)") (class "Default")
      (node (ref "USB1") (pin "B8") (pinfunction "SBUS2_B8") (pintype "passive"))
    )
    (net (code "66") (name "unconnected-(Z8-Pad4)") (class "Default")
      (node (ref "Z8") (pin "4") (pintype "passive"))
    )
    (net (code "67") (name "unconnected-(Z8-Pad6)") (class "Default")
      (node (ref "Z8") (pin "6") (pintype "passive"))
    )
  )
)
